# Kasli-SOC_MUX_I2C.net
KiCad netlist of a schematic drawn in Altium Designer
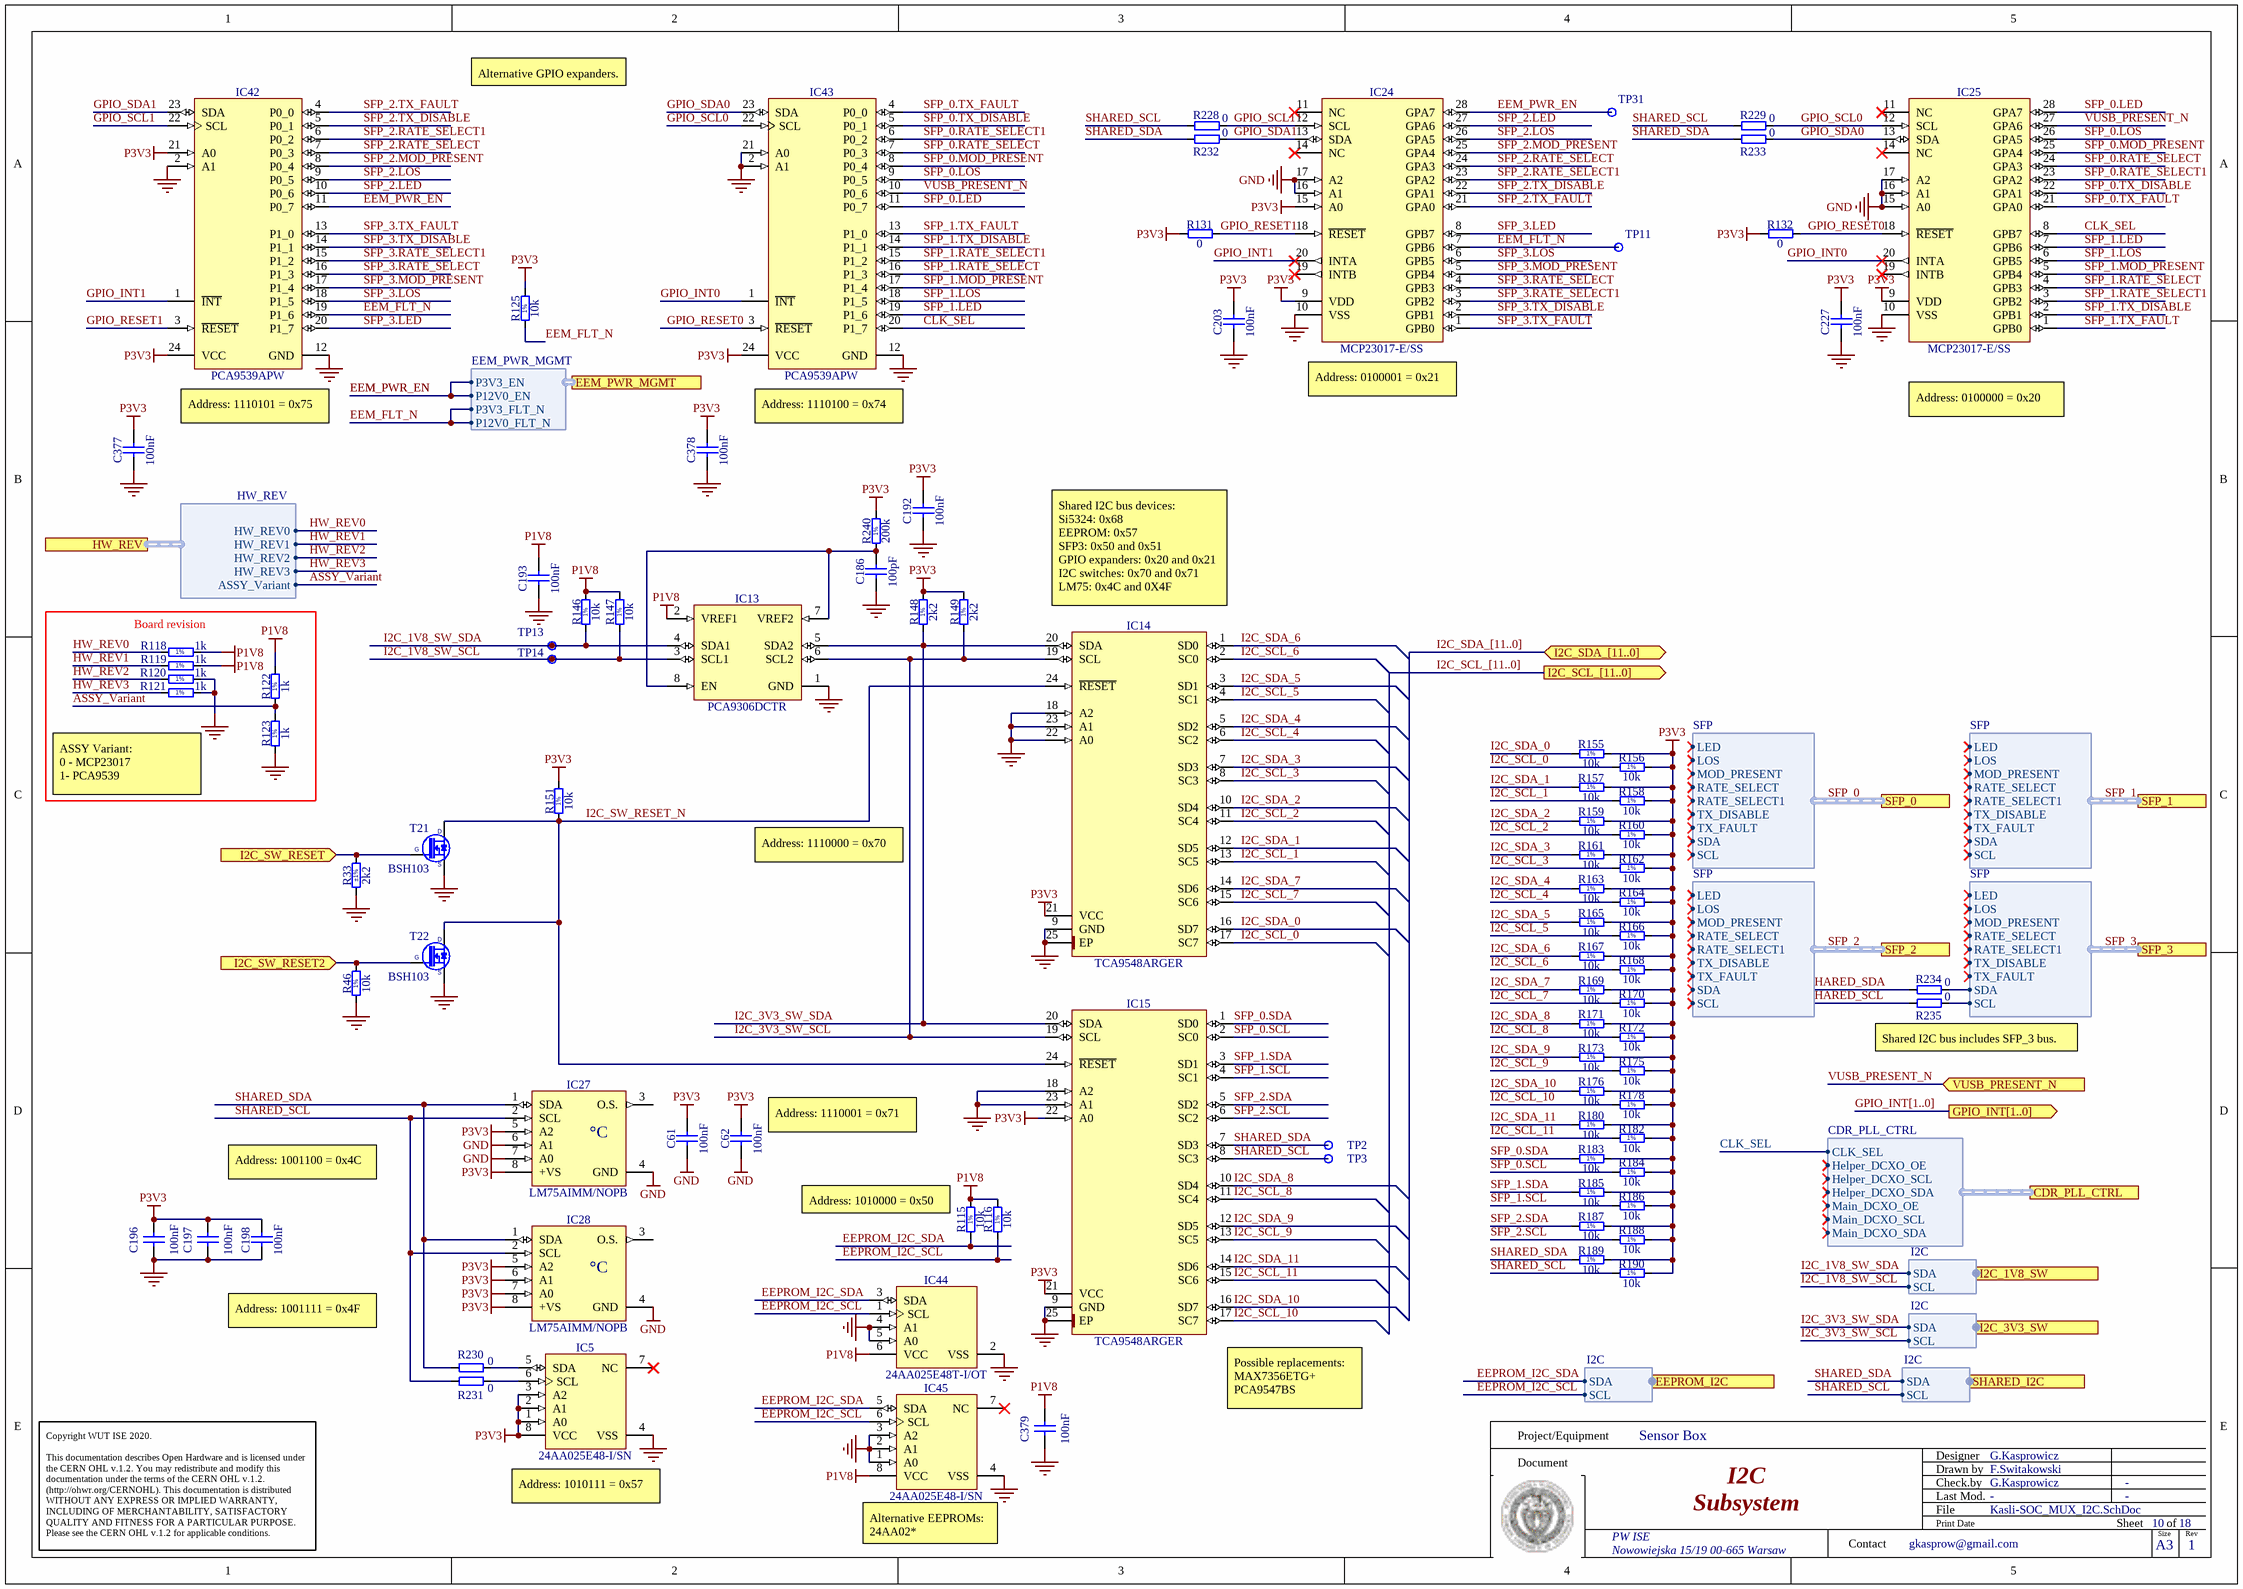
[diagram p0: Kasli-SOC_MUX_I2C.SchDoc]

(export (version "E")
  (design (tool "Eeschema 10.0.6"))
  (components
    (comp (ref "C61")
      (value "100nF")
      (footprint "CAPC1005X55N")
      (description "Non-polarised capacitor")
      (fields
        (field (name "PART NUMBER") "CC0402_100NF_16V_10%_X7R")
        (field (name "VOLTAGE") "16V")
        (field (name "AUTHOR") "CERN DEM JLC")
      )
      (libsource (lib "Capacitors") (part "Capacitor - non polarized"))
    )
    (comp (ref "C62")
      (value "100nF")
      (footprint "CAPC1005X55N")
      (description "Non-polarised capacitor")
      (fields
        (field (name "PART NUMBER") "CC0402_100NF_16V_10%_X7R")
        (field (name "VOLTAGE") "16V")
        (field (name "AUTHOR") "CERN DEM JLC")
      )
      (libsource (lib "Capacitors") (part "Capacitor - non polarized"))
    )
    (comp (ref "C186")
      (value "100pF")
      (footprint "CAPC1005X55N")
      (description "Non-polarised capacitor")
      (fields
        (field (name "PART NUMBER") "CC0402_100PF_50V_5%_C0G")
        (field (name "VOLTAGE") "50V")
        (field (name "AUTHOR") "CERN DEM JLC")
      )
      (libsource (lib "Capacitors") (part "Capacitor - non polarized"))
    )
    (comp (ref "C192")
      (value "100nF")
      (footprint "CAPC1005X55N")
      (description "Non-polarised capacitor")
      (fields
        (field (name "PART NUMBER") "CC0402_100NF_16V_10%_X7R")
        (field (name "VOLTAGE") "16V")
        (field (name "AUTHOR") "CERN DEM JLC")
      )
      (libsource (lib "Capacitors") (part "Capacitor - non polarized"))
    )
    (comp (ref "C193")
      (value "100nF")
      (footprint "CAPC1005X55N")
      (description "Non-polarised capacitor")
      (fields
        (field (name "PART NUMBER") "CC0402_100NF_16V_10%_X7R")
        (field (name "VOLTAGE") "16V")
        (field (name "AUTHOR") "CERN DEM JLC")
      )
      (libsource (lib "Capacitors") (part "Capacitor - non polarized"))
    )
    (comp (ref "C196")
      (value "100nF")
      (footprint "CAPC0603X33N")
      (description "Non-polarised capacitor")
      (fields
        (field (name "PART NUMBER") "CC0201_100NF_6.3V_10%_X5R")
        (field (name "VOLTAGE") "6.3V")
        (field (name "AUTHOR") "CERN DEM JLC")
      )
      (libsource (lib "Capacitors") (part "Capacitor - non polarized"))
    )
    (comp (ref "C197")
      (value "100nF")
      (footprint "CAPC0603X33N")
      (description "Non-polarised capacitor")
      (fields
        (field (name "PART NUMBER") "CC0201_100NF_6.3V_10%_X5R")
        (field (name "VOLTAGE") "6.3V")
        (field (name "AUTHOR") "CERN DEM JLC")
      )
      (libsource (lib "Capacitors") (part "Capacitor - non polarized"))
    )
    (comp (ref "C198")
      (value "100nF")
      (footprint "CAPC1005X55N")
      (description "Non-polarised capacitor")
      (fields
        (field (name "PART NUMBER") "CC0402_100NF_16V_10%_X7R")
        (field (name "VOLTAGE") "16V")
        (field (name "AUTHOR") "CERN DEM JLC")
      )
      (libsource (lib "Capacitors") (part "Capacitor - non polarized"))
    )
    (comp (ref "C203")
      (value "100nF")
      (footprint "CAPC1005X55N")
      (description "Non-polarised capacitor")
      (fields
        (field (name "PART NUMBER") "CC0402_100NF_16V_10%_X7R")
        (field (name "VOLTAGE") "16V")
        (field (name "AUTHOR") "CERN DEM JLC")
      )
      (libsource (lib "Capacitors") (part "Capacitor - non polarized"))
    )
    (comp (ref "C227")
      (value "100nF")
      (footprint "CAPC1005X55N")
      (description "Non-polarised capacitor")
      (fields
        (field (name "PART NUMBER") "CC0402_100NF_16V_10%_X7R")
        (field (name "VOLTAGE") "16V")
        (field (name "AUTHOR") "CERN DEM JLC")
      )
      (libsource (lib "Capacitors") (part "Capacitor - non polarized"))
    )
    (comp (ref "C377")
      (value "100nF")
      (footprint "CAPC1005X55N")
      (description "Non-polarised capacitor")
      (fields
        (field (name "PART NUMBER") "CC0402_100NF_16V_10%_X7R")
        (field (name "VOLTAGE") "16V")
        (field (name "AUTHOR") "CERN DEM JLC")
      )
      (libsource (lib "Capacitors") (part "Capacitor - non polarized"))
    )
    (comp (ref "C378")
      (value "100nF")
      (footprint "CAPC1005X55N")
      (description "Non-polarised capacitor")
      (fields
        (field (name "PART NUMBER") "CC0402_100NF_16V_10%_X7R")
        (field (name "VOLTAGE") "16V")
        (field (name "AUTHOR") "CERN DEM JLC")
      )
      (libsource (lib "Capacitors") (part "Capacitor - non polarized"))
    )
    (comp (ref "C379")
      (value "100nF")
      (footprint "CAPC1005X55N")
      (description "Non-polarised capacitor")
      (fields
        (field (name "PART NUMBER") "CC0402_100NF_16V_10%_X5R")
        (field (name "VOLTAGE") "16V")
        (field (name "AUTHOR") "CERN DEM JLC")
      )
      (libsource (lib "Capacitors") (part "Capacitor - non polarized"))
    )
    (comp (ref "IC5")
      (value "24AA025E48-I/SN")
      (footprint "SOIC127P600X175-8N")
      (description "1.7V-5.5V, 2K I2C™ Serial EEPROMs with EUI-48™ Node Identity")
      (fields (field (name "MANUFACTURER") "MICROCHIP TECHNOLOGY") (field (name "AUTHOR") "CERN DEM MR"))
      (libsource (lib "ICs And Semiconductors") (part "24AA025E48-I/SN"))
    )
    (comp (ref "IC13")
      (value "PCA9306DCTR")
      (footprint "SOP65P400X130-8N")
      (description "Dual Bidirectional I2C Bus And SMBus Voltage-Level Translator")
      (fields (field (name "MANUFACTURER") "TEXAS INSTRUMENTS") (field (name "AUTHOR") "CERN DEM JLC"))
      (libsource (lib "ICs And Semiconductors") (part "PCA9306D"))
    )
    (comp (ref "IC14")
      (value "TCA9548ARGER")
      (footprint "QFN50P400X400X100-25N-S220")
      (description "Low Voltage 8-Channel I2C Switch With Reset")
      (fields (field (name "MANUFACTURER") "TEXAS INSTRUMENTS") (field (name "AUTHOR") "CERN DEM JLC"))
      (libsource (lib "ICs And Semiconductors") (part "TCA9548ARGER"))
    )
    (comp (ref "IC15")
      (value "TCA9548ARGER")
      (footprint "QFN50P400X400X100-25N-S220")
      (description "Low Voltage 8-Channel I2C Switch With Reset")
      (fields (field (name "MANUFACTURER") "TEXAS INSTRUMENTS") (field (name "AUTHOR") "CERN DEM JLC"))
      (libsource (lib "ICs And Semiconductors") (part "TCA9548ARGER"))
    )
    (comp (ref "IC24")
      (value "MCP23017-E/SS")
      (footprint "SOP65P780X200-28N")
      (description "16-bit I/O Port Expander With Serial Interface")
      (fields (field (name "MANUFACTURER") "MICROCHIP TECHNOLOGY") (field (name "AUTHOR") "CERN DEM JLC"))
      (libsource (lib "ICs And Semiconductors") (part "MCP23017-E/SS"))
    )
    (comp (ref "IC25")
      (value "MCP23017-E/SS")
      (footprint "SOP65P780X200-28N")
      (description "16-bit I/O Port Expander With Serial Interface")
      (fields (field (name "MANUFACTURER") "MICROCHIP TECHNOLOGY") (field (name "AUTHOR") "CERN DEM JLC"))
      (libsource (lib "ICs And Semiconductors") (part "MCP23017-E/SS"))
    )
    (comp (ref "IC27")
      (value "LM75AIMM/NOPB")
      (footprint "SOP65P490X109-8N")
      (description "Digital Temperature Sensor and Thermal Watchdog with Two-Wire Interface")
      (fields (field (name "MANUFACTURER") "TEXAS INSTRUMENTS") (field (name "AUTHOR") "CERN DEM JLC"))
      (libsource (lib "ICs And Semiconductors") (part "LM75"))
    )
    (comp (ref "IC28")
      (value "LM75AIMM/NOPB")
      (footprint "SOP65P490X109-8N")
      (description "Digital Temperature Sensor and Thermal Watchdog with Two-Wire Interface")
      (fields (field (name "MANUFACTURER") "TEXAS INSTRUMENTS") (field (name "AUTHOR") "CERN DEM JLC"))
      (libsource (lib "ICs And Semiconductors") (part "LM75"))
    )
    (comp (ref "IC42")
      (value "PCA9539APW")
      (footprint "SOP65P640X110-24N")
      (description "Low-Voltage 16-Bit I2C-Bus I/O Port with Interrupt and Reset")
      (fields (field (name "MANUFACTURER") "NXP SEMICONDUCTORS") (field (name "AUTHOR") "CERN DEM JMW"))
      (libsource (lib "ICs And Semiconductors") (part "PCA9539APW"))
    )
    (comp (ref "IC43")
      (value "PCA9539APW")
      (footprint "SOP65P640X110-24N")
      (description "Low-Voltage 16-Bit I2C-Bus I/O Port with Interrupt and Reset")
      (fields (field (name "MANUFACTURER") "NXP SEMICONDUCTORS") (field (name "AUTHOR") "CERN DEM JMW"))
      (libsource (lib "ICs And Semiconductors") (part "PCA9539APW"))
    )
    (comp (ref "IC44")
      (value "24AA025E48T-I/OT")
      (footprint "SOT95P280X145-6N")
      (description "1.7V-5.5V, 2K I2C Serial EEPROM With EUI-48 Node Identity")
      (fields (field (name "MANUFACTURER") "MICROCHIP TECHNOLOGY") (field (name "AUTHOR") "CERN DEM BC"))
      (libsource (lib "ICs And Semiconductors") (part "24AA025E48T-I/OT"))
    )
    (comp (ref "IC45")
      (value "24AA025E48-I/SN")
      (footprint "SOIC127P600X175-8N")
      (description "1.7V-5.5V, 2K I2C™ Serial EEPROMs with EUI-48™ Node Identity")
      (fields (field (name "MANUFACTURER") "MICROCHIP TECHNOLOGY") (field (name "AUTHOR") "CERN DEM MR"))
      (libsource (lib "ICs And Semiconductors") (part "24AA025E48-I/SN"))
    )
    (comp (ref "R33")
      (value "2k2")
      (footprint "RESC1005X40N")
      (description "Resistor - 1%")
      (fields
        (field (name "TOLERANCE") "±1%")
        (field (name "PART NUMBER") "R0402_2K2_1%_0.0625W_100PPM")
        (field (name "POWER") "0.0625W")
        (field (name "AUTHOR") "CERN DEM JLC")
      )
      (libsource (lib "Resistors") (part "Resistor - 1%"))
    )
    (comp (ref "R46")
      (value "10k")
      (footprint "RESC1005X40N")
      (description "Resistor - 1%")
      (fields
        (field (name "PART NUMBER") "R0402_10K_1%_0.0625W_100PPM")
        (field (name "POWER") "0.0625W")
        (field (name "AUTHOR") "CERN DEM JLC")
      )
      (libsource (lib "Resistors") (part "Resistor - 1%"))
    )
    (comp (ref "R115")
      (value "10k")
      (footprint "RESC1005X40N")
      (description "Resistor - 1%")
      (fields
        (field (name "PART NUMBER") "R0402_10K_1%_0.0625W_100PPM")
        (field (name "POWER") "0.0625W")
        (field (name "AUTHOR") "CERN DEM JLC")
      )
      (libsource (lib "Resistors") (part "Resistor - 1%"))
    )
    (comp (ref "R116")
      (value "10k")
      (footprint "RESC1005X40N")
      (description "Resistor - 1%")
      (fields
        (field (name "PART NUMBER") "R0402_10K_1%_0.0625W_100PPM")
        (field (name "POWER") "0.0625W")
        (field (name "AUTHOR") "CERN DEM JLC")
      )
      (libsource (lib "Resistors") (part "Resistor - 1%"))
    )
    (comp (ref "R118")
      (value "1k")
      (footprint "RESC1005X40N")
      (description "Resistor - 1%")
      (fields
        (field (name "PART NUMBER") "R0402_1K_1%_0.0625W_100PPM")
        (field (name "POWER") "0.0625W")
        (field (name "AUTHOR") "CERN DEM JLC")
      )
      (libsource (lib "Resistors") (part "Resistor - 1%"))
    )
    (comp (ref "R119")
      (value "1k")
      (footprint "RESC1005X40N")
      (description "Resistor - 1%")
      (fields
        (field (name "PART NUMBER") "R0402_1K_1%_0.0625W_100PPM")
        (field (name "POWER") "0.0625W")
        (field (name "AUTHOR") "CERN DEM JLC")
      )
      (libsource (lib "Resistors") (part "Resistor - 1%"))
    )
    (comp (ref "R120")
      (value "1k")
      (footprint "RESC1005X40N")
      (description "Resistor - 1%")
      (fields
        (field (name "PART NUMBER") "R0402_1K_1%_0.0625W_100PPM")
        (field (name "POWER") "0.0625W")
        (field (name "AUTHOR") "CERN DEM JLC")
      )
      (libsource (lib "Resistors") (part "Resistor - 1%"))
    )
    (comp (ref "R121")
      (value "1k")
      (footprint "RESC1005X40N")
      (description "Resistor - 1%")
      (fields
        (field (name "PART NUMBER") "R0402_1K_1%_0.0625W_100PPM")
        (field (name "POWER") "0.0625W")
        (field (name "AUTHOR") "CERN DEM JLC")
      )
      (libsource (lib "Resistors") (part "Resistor - 1%"))
    )
    (comp (ref "R122")
      (value "1k")
      (footprint "RESC1005X40N")
      (description "Resistor - 1%")
      (fields
        (field (name "PART NUMBER") "R0402_1K_1%_0.0625W_100PPM")
        (field (name "POWER") "0.0625W")
        (field (name "AUTHOR") "CERN DEM JLC")
      )
      (libsource (lib "Resistors") (part "Resistor - 1%"))
    )
    (comp (ref "R123")
      (value "1k")
      (footprint "RESC1005X40N")
      (description "Resistor - 1%")
      (fields
        (field (name "PART NUMBER") "R0402_1K_1%_0.0625W_100PPM")
        (field (name "POWER") "0.0625W")
        (field (name "AUTHOR") "CERN DEM JLC")
      )
      (libsource (lib "Resistors") (part "Resistor - 1%"))
    )
    (comp (ref "R125")
      (value "10k")
      (footprint "RESC1005X40N")
      (description "Resistor - 1%")
      (fields
        (field (name "PART NUMBER") "R0402_10K_1%_0.0625W_100PPM")
        (field (name "POWER") "0.0625W")
        (field (name "AUTHOR") "CERN DEM JLC")
      )
      (libsource (lib "Resistors") (part "Resistor - 1%"))
    )
    (comp (ref "R131")
      (value "0")
      (footprint "RESC1005X40N")
      (description "Resistor")
      (fields
        (field (name "PART NUMBER") "R0402_0R_JUMPER")
        (field (name "MANUFACTURER") "GENERIC")
        (field (name "AUTHOR") "CERN DEM JLC")
      )
      (libsource (lib "Resistors") (part "Resistor"))
    )
    (comp (ref "R132")
      (value "0")
      (footprint "RESC1005X40N")
      (description "Resistor")
      (fields
        (field (name "PART NUMBER") "R0402_0R_JUMPER")
        (field (name "MANUFACTURER") "GENERIC")
        (field (name "AUTHOR") "CERN DEM JLC")
      )
      (libsource (lib "Resistors") (part "Resistor"))
    )
    (comp (ref "R146")
      (value "10k")
      (footprint "RESC1005X40N")
      (description "Resistor - 1%")
      (fields
        (field (name "PART NUMBER") "R0402_10K_1%_0.0625W_100PPM")
        (field (name "POWER") "0.0625W")
        (field (name "AUTHOR") "CERN DEM JLC")
      )
      (libsource (lib "Resistors") (part "Resistor - 1%"))
    )
    (comp (ref "R147")
      (value "10k")
      (footprint "RESC1005X40N")
      (description "Resistor - 1%")
      (fields
        (field (name "PART NUMBER") "R0402_10K_1%_0.0625W_100PPM")
        (field (name "POWER") "0.0625W")
        (field (name "AUTHOR") "CERN DEM JLC")
      )
      (libsource (lib "Resistors") (part "Resistor - 1%"))
    )
    (comp (ref "R148")
      (value "2k2")
      (footprint "RESC1005X40N")
      (description "Resistor - 1%")
      (fields
        (field (name "PART NUMBER") "R0402_2K2_1%_0.0625W_100PPM")
        (field (name "POWER") "0.0625W")
        (field (name "AUTHOR") "CERN DEM JLC")
      )
      (libsource (lib "Resistors") (part "Resistor - 1%"))
    )
    (comp (ref "R149")
      (value "2k2")
      (footprint "RESC1005X40N")
      (description "Resistor - 1%")
      (fields
        (field (name "PART NUMBER") "R0402_2K2_1%_0.0625W_100PPM")
        (field (name "POWER") "0.0625W")
        (field (name "AUTHOR") "CERN DEM JLC")
      )
      (libsource (lib "Resistors") (part "Resistor - 1%"))
    )
    (comp (ref "R151")
      (value "10k")
      (footprint "RESC1005X40N")
      (description "Resistor - 1%")
      (fields
        (field (name "PART NUMBER") "R0402_10K_1%_0.0625W_100PPM")
        (field (name "POWER") "0.0625W")
        (field (name "AUTHOR") "CERN DEM JLC")
      )
      (libsource (lib "Resistors") (part "Resistor - 1%"))
    )
    (comp (ref "R155")
      (value "10k")
      (footprint "RESC1005X40N")
      (description "Resistor - 1%")
      (fields
        (field (name "PART NUMBER") "R0402_10K_1%_0.0625W_100PPM")
        (field (name "POWER") "0.0625W")
        (field (name "AUTHOR") "CERN DEM JLC")
      )
      (libsource (lib "Resistors") (part "Resistor - 1%"))
    )
    (comp (ref "R156")
      (value "10k")
      (footprint "RESC1005X40N")
      (description "Resistor - 1%")
      (fields
        (field (name "PART NUMBER") "R0402_10K_1%_0.0625W_100PPM")
        (field (name "POWER") "0.0625W")
        (field (name "AUTHOR") "CERN DEM JLC")
      )
      (libsource (lib "Resistors") (part "Resistor - 1%"))
    )
    (comp (ref "R157")
      (value "10k")
      (footprint "RESC1005X40N")
      (description "Resistor - 1%")
      (fields
        (field (name "PART NUMBER") "R0402_10K_1%_0.0625W_100PPM")
        (field (name "POWER") "0.0625W")
        (field (name "AUTHOR") "CERN DEM JLC")
      )
      (libsource (lib "Resistors") (part "Resistor - 1%"))
    )
    (comp (ref "R158")
      (value "10k")
      (footprint "RESC1005X40N")
      (description "Resistor - 1%")
      (fields
        (field (name "PART NUMBER") "R0402_10K_1%_0.0625W_100PPM")
        (field (name "POWER") "0.0625W")
        (field (name "AUTHOR") "CERN DEM JLC")
      )
      (libsource (lib "Resistors") (part "Resistor - 1%"))
    )
    (comp (ref "R159")
      (value "10k")
      (footprint "RESC1005X40N")
      (description "Resistor - 1%")
      (fields
        (field (name "PART NUMBER") "R0402_10K_1%_0.0625W_100PPM")
        (field (name "POWER") "0.0625W")
        (field (name "AUTHOR") "CERN DEM JLC")
      )
      (libsource (lib "Resistors") (part "Resistor - 1%"))
    )
    (comp (ref "R160")
      (value "10k")
      (footprint "RESC1005X40N")
      (description "Resistor - 1%")
      (fields
        (field (name "PART NUMBER") "R0402_10K_1%_0.0625W_100PPM")
        (field (name "POWER") "0.0625W")
        (field (name "AUTHOR") "CERN DEM JLC")
      )
      (libsource (lib "Resistors") (part "Resistor - 1%"))
    )
    (comp (ref "R161")
      (value "10k")
      (footprint "RESC1005X40N")
      (description "Resistor - 1%")
      (fields
        (field (name "PART NUMBER") "R0402_10K_1%_0.0625W_100PPM")
        (field (name "POWER") "0.0625W")
        (field (name "AUTHOR") "CERN DEM JLC")
      )
      (libsource (lib "Resistors") (part "Resistor - 1%"))
    )
    (comp (ref "R162")
      (value "10k")
      (footprint "RESC1005X40N")
      (description "Resistor - 1%")
      (fields
        (field (name "PART NUMBER") "R0402_10K_1%_0.0625W_100PPM")
        (field (name "POWER") "0.0625W")
        (field (name "AUTHOR") "CERN DEM JLC")
      )
      (libsource (lib "Resistors") (part "Resistor - 1%"))
    )
    (comp (ref "R163")
      (value "10k")
      (footprint "RESC1005X40N")
      (description "Resistor - 1%")
      (fields
        (field (name "PART NUMBER") "R0402_10K_1%_0.0625W_100PPM")
        (field (name "POWER") "0.0625W")
        (field (name "AUTHOR") "CERN DEM JLC")
      )
      (libsource (lib "Resistors") (part "Resistor - 1%"))
    )
    (comp (ref "R164")
      (value "10k")
      (footprint "RESC1005X40N")
      (description "Resistor - 1%")
      (fields
        (field (name "PART NUMBER") "R0402_10K_1%_0.0625W_100PPM")
        (field (name "POWER") "0.0625W")
        (field (name "AUTHOR") "CERN DEM JLC")
      )
      (libsource (lib "Resistors") (part "Resistor - 1%"))
    )
    (comp (ref "R165")
      (value "10k")
      (footprint "RESC1005X40N")
      (description "Resistor - 1%")
      (fields
        (field (name "PART NUMBER") "R0402_10K_1%_0.0625W_100PPM")
        (field (name "POWER") "0.0625W")
        (field (name "AUTHOR") "CERN DEM JLC")
      )
      (libsource (lib "Resistors") (part "Resistor - 1%"))
    )
    (comp (ref "R166")
      (value "10k")
      (footprint "RESC1005X40N")
      (description "Resistor - 1%")
      (fields
        (field (name "PART NUMBER") "R0402_10K_1%_0.0625W_100PPM")
        (field (name "POWER") "0.0625W")
        (field (name "AUTHOR") "CERN DEM JLC")
      )
      (libsource (lib "Resistors") (part "Resistor - 1%"))
    )
    (comp (ref "R167")
      (value "10k")
      (footprint "RESC1005X40N")
      (description "Resistor - 1%")
      (fields
        (field (name "PART NUMBER") "R0402_10K_1%_0.0625W_100PPM")
        (field (name "POWER") "0.0625W")
        (field (name "AUTHOR") "CERN DEM JLC")
      )
      (libsource (lib "Resistors") (part "Resistor - 1%"))
    )
    (comp (ref "R168")
      (value "10k")
      (footprint "RESC1005X40N")
      (description "Resistor - 1%")
      (fields
        (field (name "PART NUMBER") "R0402_10K_1%_0.0625W_100PPM")
        (field (name "POWER") "0.0625W")
        (field (name "AUTHOR") "CERN DEM JLC")
      )
      (libsource (lib "Resistors") (part "Resistor - 1%"))
    )
    (comp (ref "R169")
      (value "10k")
      (footprint "RESC1005X40N")
      (description "Resistor - 1%")
      (fields
        (field (name "PART NUMBER") "R0402_10K_1%_0.0625W_100PPM")
        (field (name "POWER") "0.0625W")
        (field (name "AUTHOR") "CERN DEM JLC")
      )
      (libsource (lib "Resistors") (part "Resistor - 1%"))
    )
    (comp (ref "R170")
      (value "10k")
      (footprint "RESC1005X40N")
      (description "Resistor - 1%")
      (fields
        (field (name "PART NUMBER") "R0402_10K_1%_0.0625W_100PPM")
        (field (name "POWER") "0.0625W")
        (field (name "AUTHOR") "CERN DEM JLC")
      )
      (libsource (lib "Resistors") (part "Resistor - 1%"))
    )
    (comp (ref "R171")
      (value "10k")
      (footprint "RESC1005X40N")
      (description "Resistor - 1%")
      (fields
        (field (name "PART NUMBER") "R0402_10K_1%_0.0625W_100PPM")
        (field (name "POWER") "0.0625W")
        (field (name "AUTHOR") "CERN DEM JLC")
      )
      (libsource (lib "Resistors") (part "Resistor - 1%"))
    )
    (comp (ref "R172")
      (value "10k")
      (footprint "RESC1005X40N")
      (description "Resistor - 1%")
      (fields
        (field (name "PART NUMBER") "R0402_10K_1%_0.0625W_100PPM")
        (field (name "POWER") "0.0625W")
        (field (name "AUTHOR") "CERN DEM JLC")
      )
      (libsource (lib "Resistors") (part "Resistor - 1%"))
    )
    (comp (ref "R173")
      (value "10k")
      (footprint "RESC1005X40N")
      (description "Resistor - 1%")
      (fields
        (field (name "PART NUMBER") "R0402_10K_1%_0.0625W_100PPM")
        (field (name "POWER") "0.0625W")
        (field (name "AUTHOR") "CERN DEM JLC")
      )
      (libsource (lib "Resistors") (part "Resistor - 1%"))
    )
    (comp (ref "R175")
      (value "10k")
      (footprint "RESC1005X40N")
      (description "Resistor - 1%")
      (fields
        (field (name "PART NUMBER") "R0402_10K_1%_0.0625W_100PPM")
        (field (name "POWER") "0.0625W")
        (field (name "AUTHOR") "CERN DEM JLC")
      )
      (libsource (lib "Resistors") (part "Resistor - 1%"))
    )
    (comp (ref "R176")
      (value "10k")
      (footprint "RESC1005X40N")
      (description "Resistor - 1%")
      (fields
        (field (name "PART NUMBER") "R0402_10K_1%_0.0625W_100PPM")
        (field (name "POWER") "0.0625W")
        (field (name "AUTHOR") "CERN DEM JLC")
      )
      (libsource (lib "Resistors") (part "Resistor - 1%"))
    )
    (comp (ref "R178")
      (value "10k")
      (footprint "RESC1005X40N")
      (description "Resistor - 1%")
      (fields
        (field (name "PART NUMBER") "R0402_10K_1%_0.0625W_100PPM")
        (field (name "POWER") "0.0625W")
        (field (name "AUTHOR") "CERN DEM JLC")
      )
      (libsource (lib "Resistors") (part "Resistor - 1%"))
    )
    (comp (ref "R180")
      (value "10k")
      (footprint "RESC1005X40N")
      (description "Resistor - 1%")
      (fields
        (field (name "PART NUMBER") "R0402_10K_1%_0.0625W_100PPM")
        (field (name "POWER") "0.0625W")
        (field (name "AUTHOR") "CERN DEM JLC")
      )
      (libsource (lib "Resistors") (part "Resistor - 1%"))
    )
    (comp (ref "R182")
      (value "10k")
      (footprint "RESC1005X40N")
      (description "Resistor - 1%")
      (fields
        (field (name "PART NUMBER") "R0402_10K_1%_0.0625W_100PPM")
        (field (name "POWER") "0.0625W")
        (field (name "AUTHOR") "CERN DEM JLC")
      )
      (libsource (lib "Resistors") (part "Resistor - 1%"))
    )
    (comp (ref "R183")
      (value "10k")
      (footprint "RESC1005X40N")
      (description "Resistor - 1%")
      (fields
        (field (name "PART NUMBER") "R0402_10K_1%_0.0625W_100PPM")
        (field (name "POWER") "0.0625W")
        (field (name "AUTHOR") "CERN DEM JLC")
      )
      (libsource (lib "Resistors") (part "Resistor - 1%"))
    )
    (comp (ref "R184")
      (value "10k")
      (footprint "RESC1005X40N")
      (description "Resistor - 1%")
      (fields
        (field (name "PART NUMBER") "R0402_10K_1%_0.0625W_100PPM")
        (field (name "POWER") "0.0625W")
        (field (name "AUTHOR") "CERN DEM JLC")
      )
      (libsource (lib "Resistors") (part "Resistor - 1%"))
    )
    (comp (ref "R185")
      (value "10k")
      (footprint "RESC1005X40N")
      (description "Resistor - 1%")
      (fields
        (field (name "PART NUMBER") "R0402_10K_1%_0.0625W_100PPM")
        (field (name "POWER") "0.0625W")
        (field (name "AUTHOR") "CERN DEM JLC")
      )
      (libsource (lib "Resistors") (part "Resistor - 1%"))
    )
    (comp (ref "R186")
      (value "10k")
      (footprint "RESC1005X40N")
      (description "Resistor - 1%")
      (fields
        (field (name "PART NUMBER") "R0402_10K_1%_0.0625W_100PPM")
        (field (name "POWER") "0.0625W")
        (field (name "AUTHOR") "CERN DEM JLC")
      )
      (libsource (lib "Resistors") (part "Resistor - 1%"))
    )
    (comp (ref "R187")
      (value "10k")
      (footprint "RESC1005X40N")
      (description "Resistor - 1%")
      (fields
        (field (name "PART NUMBER") "R0402_10K_1%_0.0625W_100PPM")
        (field (name "POWER") "0.0625W")
        (field (name "AUTHOR") "CERN DEM JLC")
      )
      (libsource (lib "Resistors") (part "Resistor - 1%"))
    )
    (comp (ref "R188")
      (value "10k")
      (footprint "RESC1005X40N")
      (description "Resistor - 1%")
      (fields
        (field (name "PART NUMBER") "R0402_10K_1%_0.0625W_100PPM")
        (field (name "POWER") "0.0625W")
        (field (name "AUTHOR") "CERN DEM JLC")
      )
      (libsource (lib "Resistors") (part "Resistor - 1%"))
    )
    (comp (ref "R189")
      (value "10k")
      (footprint "RESC1005X40N")
      (description "Resistor - 1%")
      (fields
        (field (name "PART NUMBER") "R0402_10K_1%_0.0625W_100PPM")
        (field (name "POWER") "0.0625W")
        (field (name "AUTHOR") "CERN DEM JLC")
      )
      (libsource (lib "Resistors") (part "Resistor - 1%"))
    )
    (comp (ref "R190")
      (value "10k")
      (footprint "RESC1005X40N")
      (description "Resistor - 1%")
      (fields
        (field (name "PART NUMBER") "R0402_10K_1%_0.0625W_100PPM")
        (field (name "POWER") "0.0625W")
        (field (name "AUTHOR") "CERN DEM JLC")
      )
      (libsource (lib "Resistors") (part "Resistor - 1%"))
    )
    (comp (ref "R228")
      (value "0")
      (footprint "RESC1005X40N")
      (description "Resistor")
      (fields
        (field (name "PART NUMBER") "R0402_0R_JUMPER")
        (field (name "MANUFACTURER") "GENERIC")
        (field (name "AUTHOR") "CERN DEM JLC")
      )
      (libsource (lib "Resistors") (part "Resistor"))
    )
    (comp (ref "R229")
      (value "0")
      (footprint "RESC1005X40N")
      (description "Resistor")
      (fields
        (field (name "PART NUMBER") "R0402_0R_JUMPER")
        (field (name "MANUFACTURER") "GENERIC")
        (field (name "AUTHOR") "CERN DEM JLC")
      )
      (libsource (lib "Resistors") (part "Resistor"))
    )
    (comp (ref "R230")
      (value "0")
      (footprint "RESC1005X40N")
      (description "Resistor")
      (fields
        (field (name "PART NUMBER") "R0402_0R_JUMPER")
        (field (name "MANUFACTURER") "GENERIC")
        (field (name "AUTHOR") "CERN DEM JLC")
      )
      (libsource (lib "Resistors") (part "Resistor"))
    )
    (comp (ref "R231")
      (value "0")
      (footprint "RESC1005X40N")
      (description "Resistor")
      (fields
        (field (name "PART NUMBER") "R0402_0R_JUMPER")
        (field (name "MANUFACTURER") "GENERIC")
        (field (name "AUTHOR") "CERN DEM JLC")
      )
      (libsource (lib "Resistors") (part "Resistor"))
    )
    (comp (ref "R232")
      (value "0")
      (footprint "RESC1005X40N")
      (description "Resistor")
      (fields
        (field (name "PART NUMBER") "R0402_0R_JUMPER")
        (field (name "MANUFACTURER") "GENERIC")
        (field (name "AUTHOR") "CERN DEM JLC")
      )
      (libsource (lib "Resistors") (part "Resistor"))
    )
    (comp (ref "R233")
      (value "0")
      (footprint "RESC1005X40N")
      (description "Resistor")
      (fields
        (field (name "PART NUMBER") "R0402_0R_JUMPER")
        (field (name "MANUFACTURER") "GENERIC")
        (field (name "AUTHOR") "CERN DEM JLC")
      )
      (libsource (lib "Resistors") (part "Resistor"))
    )
    (comp (ref "R234")
      (value "0")
      (footprint "RESC1005X40N")
      (description "Resistor")
      (fields
        (field (name "PART NUMBER") "R0402_0R_JUMPER")
        (field (name "MANUFACTURER") "GENERIC")
        (field (name "AUTHOR") "CERN DEM JLC")
      )
      (libsource (lib "Resistors") (part "Resistor"))
    )
    (comp (ref "R235")
      (value "0")
      (footprint "RESC1005X40N")
      (description "Resistor")
      (fields
        (field (name "PART NUMBER") "R0402_0R_JUMPER")
        (field (name "MANUFACTURER") "GENERIC")
        (field (name "AUTHOR") "CERN DEM JLC")
      )
      (libsource (lib "Resistors") (part "Resistor"))
    )
    (comp (ref "R240")
      (value "200k")
      (footprint "RESC1005X40N")
      (description "Resistor - 1%")
      (fields
        (field (name "PART NUMBER") "R0402_200K_1%_0.0625W_100PPM")
        (field (name "POWER") "0.0625W")
        (field (name "AUTHOR") "CERN DEM JLC")
      )
      (libsource (lib "Resistors") (part "Resistor - 1%"))
    )
    (comp (ref "T21")
      (value "BSH103")
      (footprint "SOT95P230X110-3N")
      (description "N-CHANNEL MOSFET WITH DIODE")
      (fields (field (name "MANUFACTURER") "NEXPERIA") (field (name "AUTHOR") "CERN DEM JLC"))
      (libsource (lib "ICs And Semiconductors") (part "N-MOSFET-D 1G 2S 3D"))
    )
    (comp (ref "T22")
      (value "BSH103")
      (footprint "SOT95P230X110-3N")
      (description "N-CHANNEL MOSFET WITH DIODE")
      (fields (field (name "MANUFACTURER") "NEXPERIA") (field (name "AUTHOR") "CERN DEM JLC"))
      (libsource (lib "ICs And Semiconductors") (part "N-MOSFET-D 1G 2S 3D"))
    )
    (comp (ref "TP2")
      (value "Si5324 I2C SDA")
      (footprint "TPS127")
      (description "Test Point")
      (fields (field (name "PART NUMBER") "SMD_PAD_1.27X1.27MM") (field (name "AUTHOR") "CERN DEM JLC"))
      (libsource (lib "Eletro-mechanical") (part "Test Point"))
    )
    (comp (ref "TP3")
      (value "Si5324 I2C SCL")
      (footprint "TPS127")
      (description "Test Point")
      (fields (field (name "PART NUMBER") "SMD_PAD_1.27X1.27MM") (field (name "AUTHOR") "CERN DEM JLC"))
      (libsource (lib "Eletro-mechanical") (part "Test Point"))
    )
    (comp (ref "TP11")
      (value "I2C SW SCL")
      (footprint "TPS127")
      (description "Test Point")
      (fields (field (name "PART NUMBER") "SMD_PAD_1.27X1.27MM") (field (name "AUTHOR") "CERN DEM JLC"))
      (libsource (lib "Eletro-mechanical") (part "Test Point"))
    )
    (comp (ref "TP13")
      (value "I2C SW SDA")
      (footprint "TPS127")
      (description "Test Point")
      (fields (field (name "PART NUMBER") "SMD_PAD_1.27X1.27MM") (field (name "AUTHOR") "CERN DEM JLC"))
      (libsource (lib "Eletro-mechanical") (part "Test Point"))
    )
    (comp (ref "TP14")
      (value "I2C SW SCL")
      (footprint "TPS127")
      (description "Test Point")
      (fields (field (name "PART NUMBER") "SMD_PAD_1.27X1.27MM") (field (name "AUTHOR") "CERN DEM JLC"))
      (libsource (lib "Eletro-mechanical") (part "Test Point"))
    )
    (comp (ref "TP31")
      (value "I2C SW SCL")
      (footprint "TPS127")
      (description "Test Point")
      (fields (field (name "PART NUMBER") "SMD_PAD_1.27X1.27MM") (field (name "AUTHOR") "CERN DEM JLC"))
      (libsource (lib "Eletro-mechanical") (part "Test Point"))
    )
  )
  (nets
    (net (code "9") (name "/ASSY_Variant") (class "Default")
      (node (ref "R122") (pin "1") (pinfunction "1_1") (pintype "passive"))
      (node (ref "R123") (pin "2") (pinfunction "2_2") (pintype "passive"))
    )
    (net (code "10") (name "/CLK_SEL") (class "Default")
      (node (ref "IC25") (pin "8") (pinfunction "GPB7_8") (pintype "bidirectional"))
      (node (ref "IC43") (pin "20") (pinfunction "P1_7_20") (pintype "bidirectional"))
    )
    (net (code "11") (name "/EEM_FLT_N") (class "Default")
      (node (ref "IC24") (pin "7") (pinfunction "GPB6_7") (pintype "bidirectional"))
      (node (ref "IC42") (pin "19") (pinfunction "P1_6_19") (pintype "bidirectional"))
      (node (ref "R125") (pin "1") (pinfunction "1_1") (pintype "passive"))
      (node (ref "TP11") (pin "1") (pinfunction "1_1") (pintype "bidirectional"))
    )
    (net (code "12") (name "/EEM_PWR_EN") (class "Default")
      (node (ref "IC24") (pin "28") (pinfunction "GPA7_28") (pintype "bidirectional"))
      (node (ref "IC42") (pin "11") (pinfunction "P0_7_11") (pintype "bidirectional"))
      (node (ref "TP31") (pin "1") (pinfunction "1_1") (pintype "bidirectional"))
    )
    (net (code "13") (name "/EEPROM_I2C_SCL") (class "Default")
      (node (ref "IC44") (pin "1") (pinfunction "SCL_1") (pintype "input"))
      (node (ref "IC45") (pin "6") (pinfunction "SCL_6") (pintype "input"))
      (node (ref "R116") (pin "1") (pinfunction "1_1") (pintype "passive"))
    )
    (net (code "14") (name "/EEPROM_I2C_SDA") (class "Default")
      (node (ref "IC44") (pin "3") (pinfunction "SDA_3") (pintype "bidirectional"))
      (node (ref "IC45") (pin "5") (pinfunction "SDA_5") (pintype "bidirectional"))
      (node (ref "R115") (pin "1") (pinfunction "1_1") (pintype "passive"))
    )
    (net (code "15") (name "/GPIO_INT0") (class "Default")
      (node (ref "IC25") (pin "20") (pinfunction "INTA_20") (pintype "output"))
      (node (ref "IC43") (pin "1") (pinfunction "~{INT}_1") (pintype "open_collector"))
    )
    (net (code "16") (name "/GPIO_INT1") (class "Default")
      (node (ref "IC24") (pin "20") (pinfunction "INTA_20") (pintype "output"))
      (node (ref "IC42") (pin "1") (pinfunction "~{INT}_1") (pintype "open_collector"))
    )
    (net (code "18") (name "/GPIO_RESET0") (class "Default")
      (node (ref "IC25") (pin "18") (pinfunction "~{RESET}_18") (pintype "input"))
      (node (ref "IC43") (pin "3") (pinfunction "~{RESET}_3") (pintype "input"))
      (node (ref "R132") (pin "2") (pinfunction "2_2") (pintype "passive"))
    )
    (net (code "19") (name "/GPIO_RESET1") (class "Default")
      (node (ref "IC24") (pin "18") (pinfunction "~{RESET}_18") (pintype "input"))
      (node (ref "IC42") (pin "3") (pinfunction "~{RESET}_3") (pintype "input"))
      (node (ref "R131") (pin "2") (pinfunction "2_2") (pintype "passive"))
    )
    (net (code "20") (name "/GPIO_SCL0") (class "Default")
      (node (ref "IC25") (pin "12") (pinfunction "SCL_12") (pintype "input"))
      (node (ref "IC43") (pin "22") (pinfunction "SCL_22") (pintype "input"))
      (node (ref "R229") (pin "2") (pinfunction "2_2") (pintype "passive"))
    )
    (net (code "21") (name "/GPIO_SCL1") (class "Default")
      (node (ref "IC24") (pin "12") (pinfunction "SCL_12") (pintype "input"))
      (node (ref "IC42") (pin "22") (pinfunction "SCL_22") (pintype "input"))
      (node (ref "R228") (pin "2") (pinfunction "2_2") (pintype "passive"))
    )
    (net (code "22") (name "/GPIO_SDA0") (class "Default")
      (node (ref "IC25") (pin "13") (pinfunction "SDA_13") (pintype "bidirectional"))
      (node (ref "IC43") (pin "23") (pinfunction "SDA_23") (pintype "bidirectional"))
      (node (ref "R233") (pin "2") (pinfunction "2_2") (pintype "passive"))
    )
    (net (code "23") (name "/GPIO_SDA1") (class "Default")
      (node (ref "IC24") (pin "13") (pinfunction "SDA_13") (pintype "bidirectional"))
      (node (ref "IC42") (pin "23") (pinfunction "SDA_23") (pintype "bidirectional"))
      (node (ref "R232") (pin "2") (pinfunction "2_2") (pintype "passive"))
    )
    (net (code "24") (name "/HW_REV0") (class "Default")
      (node (ref "R118") (pin "1") (pinfunction "1_1") (pintype "passive"))
    )
    (net (code "25") (name "/HW_REV1") (class "Default")
      (node (ref "R119") (pin "1") (pinfunction "1_1") (pintype "passive"))
    )
    (net (code "26") (name "/HW_REV2") (class "Default")
      (node (ref "R120") (pin "1") (pinfunction "1_1") (pintype "passive"))
    )
    (net (code "27") (name "/HW_REV3") (class "Default")
      (node (ref "R121") (pin "1") (pinfunction "1_1") (pintype "passive"))
    )
    (net (code "28") (name "/I2C_1V8_SW_SCL") (class "Default")
      (node (ref "IC13") (pin "3") (pinfunction "SCL1_3") (pintype "bidirectional"))
      (node (ref "R147") (pin "1") (pinfunction "1_1") (pintype "passive"))
      (node (ref "TP14") (pin "1") (pinfunction "1_1") (pintype "bidirectional"))
    )
    (net (code "29") (name "/I2C_1V8_SW_SDA") (class "Default")
      (node (ref "IC13") (pin "4") (pinfunction "SDA1_4") (pintype "bidirectional"))
      (node (ref "R146") (pin "1") (pinfunction "1_1") (pintype "passive"))
      (node (ref "TP13") (pin "1") (pinfunction "1_1") (pintype "bidirectional"))
    )
    (net (code "30") (name "/I2C_3V3_SW_SCL") (class "Default")
      (node (ref "IC13") (pin "6") (pinfunction "SCL2_6") (pintype "bidirectional"))
      (node (ref "IC14") (pin "19") (pinfunction "SCL_19") (pintype "bidirectional"))
      (node (ref "IC15") (pin "19") (pinfunction "SCL_19") (pintype "bidirectional"))
      (node (ref "R149") (pin "1") (pinfunction "1_1") (pintype "passive"))
    )
    (net (code "31") (name "/I2C_3V3_SW_SDA") (class "Default")
      (node (ref "IC13") (pin "5") (pinfunction "SDA2_5") (pintype "bidirectional"))
      (node (ref "IC14") (pin "20") (pinfunction "SDA_20") (pintype "bidirectional"))
      (node (ref "IC15") (pin "20") (pinfunction "SDA_20") (pintype "bidirectional"))
      (node (ref "R148") (pin "1") (pinfunction "1_1") (pintype "passive"))
    )
    (net (code "32") (name "/I2C_SCL_0") (class "Default")
      (node (ref "IC14") (pin "17") (pinfunction "SC7_17") (pintype "bidirectional"))
      (node (ref "R156") (pin "1") (pinfunction "1_1") (pintype "passive"))
    )
    (net (code "33") (name "/I2C_SCL_1") (class "Default")
      (node (ref "IC14") (pin "13") (pinfunction "SC5_13") (pintype "bidirectional"))
      (node (ref "R158") (pin "1") (pinfunction "1_1") (pintype "passive"))
    )
    (net (code "34") (name "/I2C_SCL_2") (class "Default")
      (node (ref "IC14") (pin "11") (pinfunction "SC4_11") (pintype "bidirectional"))
      (node (ref "R160") (pin "1") (pinfunction "1_1") (pintype "passive"))
    )
    (net (code "35") (name "/I2C_SCL_3") (class "Default")
      (node (ref "IC14") (pin "8") (pinfunction "SC3_8") (pintype "bidirectional"))
      (node (ref "R162") (pin "1") (pinfunction "1_1") (pintype "passive"))
    )
    (net (code "36") (name "/I2C_SCL_4") (class "Default")
      (node (ref "IC14") (pin "6") (pinfunction "SC2_6") (pintype "bidirectional"))
      (node (ref "R164") (pin "1") (pinfunction "1_1") (pintype "passive"))
    )
    (net (code "37") (name "/I2C_SCL_5") (class "Default")
      (node (ref "IC14") (pin "4") (pinfunction "SC1_4") (pintype "bidirectional"))
      (node (ref "R166") (pin "1") (pinfunction "1_1") (pintype "passive"))
    )
    (net (code "38") (name "/I2C_SCL_6") (class "Default")
      (node (ref "IC14") (pin "2") (pinfunction "SC0_2") (pintype "bidirectional"))
      (node (ref "R168") (pin "1") (pinfunction "1_1") (pintype "passive"))
    )
    (net (code "39") (name "/I2C_SCL_7") (class "Default")
      (node (ref "IC14") (pin "15") (pinfunction "SC6_15") (pintype "bidirectional"))
      (node (ref "R170") (pin "1") (pinfunction "1_1") (pintype "passive"))
    )
    (net (code "40") (name "/I2C_SCL_8") (class "Default")
      (node (ref "IC15") (pin "11") (pinfunction "SC4_11") (pintype "bidirectional"))
      (node (ref "R172") (pin "1") (pinfunction "1_1") (pintype "passive"))
    )
    (net (code "41") (name "/I2C_SCL_9") (class "Default")
      (node (ref "IC15") (pin "13") (pinfunction "SC5_13") (pintype "bidirectional"))
      (node (ref "R175") (pin "1") (pinfunction "1_1") (pintype "passive"))
    )
    (net (code "42") (name "/I2C_SCL_10") (class "Default")
      (node (ref "IC15") (pin "17") (pinfunction "SC7_17") (pintype "bidirectional"))
      (node (ref "R178") (pin "1") (pinfunction "1_1") (pintype "passive"))
    )
    (net (code "43") (name "/I2C_SCL_11") (class "Default")
      (node (ref "IC15") (pin "15") (pinfunction "SC6_15") (pintype "bidirectional"))
      (node (ref "R182") (pin "1") (pinfunction "1_1") (pintype "passive"))
    )
    (net (code "45") (name "/I2C_SDA_0") (class "Default")
      (node (ref "IC14") (pin "16") (pinfunction "SD7_16") (pintype "bidirectional"))
      (node (ref "R155") (pin "1") (pinfunction "1_1") (pintype "passive"))
    )
    (net (code "46") (name "/I2C_SDA_1") (class "Default")
      (node (ref "IC14") (pin "12") (pinfunction "SD5_12") (pintype "bidirectional"))
      (node (ref "R157") (pin "1") (pinfunction "1_1") (pintype "passive"))
    )
    (net (code "47") (name "/I2C_SDA_2") (class "Default")
      (node (ref "IC14") (pin "10") (pinfunction "SD4_10") (pintype "bidirectional"))
      (node (ref "R159") (pin "1") (pinfunction "1_1") (pintype "passive"))
    )
    (net (code "48") (name "/I2C_SDA_3") (class "Default")
      (node (ref "IC14") (pin "7") (pinfunction "SD3_7") (pintype "bidirectional"))
      (node (ref "R161") (pin "1") (pinfunction "1_1") (pintype "passive"))
    )
    (net (code "49") (name "/I2C_SDA_4") (class "Default")
      (node (ref "IC14") (pin "5") (pinfunction "SD2_5") (pintype "bidirectional"))
      (node (ref "R163") (pin "1") (pinfunction "1_1") (pintype "passive"))
    )
    (net (code "50") (name "/I2C_SDA_5") (class "Default")
      (node (ref "IC14") (pin "3") (pinfunction "SD1_3") (pintype "bidirectional"))
      (node (ref "R165") (pin "1") (pinfunction "1_1") (pintype "passive"))
    )
    (net (code "51") (name "/I2C_SDA_6") (class "Default")
      (node (ref "IC14") (pin "1") (pinfunction "SD0_1") (pintype "bidirectional"))
      (node (ref "R167") (pin "1") (pinfunction "1_1") (pintype "passive"))
    )
    (net (code "52") (name "/I2C_SDA_7") (class "Default")
      (node (ref "IC14") (pin "14") (pinfunction "SD6_14") (pintype "bidirectional"))
      (node (ref "R169") (pin "1") (pinfunction "1_1") (pintype "passive"))
    )
    (net (code "53") (name "/I2C_SDA_8") (class "Default")
      (node (ref "IC15") (pin "10") (pinfunction "SD4_10") (pintype "bidirectional"))
      (node (ref "R171") (pin "1") (pinfunction "1_1") (pintype "passive"))
    )
    (net (code "54") (name "/I2C_SDA_9") (class "Default")
      (node (ref "IC15") (pin "12") (pinfunction "SD5_12") (pintype "bidirectional"))
      (node (ref "R173") (pin "1") (pinfunction "1_1") (pintype "passive"))
    )
    (net (code "55") (name "/I2C_SDA_10") (class "Default")
      (node (ref "IC15") (pin "16") (pinfunction "SD7_16") (pintype "bidirectional"))
      (node (ref "R176") (pin "1") (pinfunction "1_1") (pintype "passive"))
    )
    (net (code "56") (name "/I2C_SDA_11") (class "Default")
      (node (ref "IC15") (pin "14") (pinfunction "SD6_14") (pintype "bidirectional"))
      (node (ref "R180") (pin "1") (pinfunction "1_1") (pintype "passive"))
    )
    (net (code "58") (name "/I2C_SW_RESET") (class "Default")
      (node (ref "R33") (pin "2") (pinfunction "2_2") (pintype "passive"))
      (node (ref "T21") (pin "1") (pinfunction "G_1") (pintype "passive"))
    )
    (net (code "59") (name "/I2C_SW_RESET2") (class "Default")
      (node (ref "R46") (pin "2") (pinfunction "2_2") (pintype "passive"))
      (node (ref "T22") (pin "1") (pinfunction "G_1") (pintype "passive"))
    )
    (net (code "60") (name "/I2C_SW_RESET_N") (class "Default")
      (node (ref "IC14") (pin "24") (pinfunction "~{RESET}_24") (pintype "input"))
      (node (ref "IC15") (pin "24") (pinfunction "~{RESET}_24") (pintype "input"))
      (node (ref "R151") (pin "1") (pinfunction "1_1") (pintype "passive"))
      (node (ref "T21") (pin "3") (pinfunction "D_3") (pintype "passive"))
      (node (ref "T22") (pin "3") (pinfunction "D_3") (pintype "passive"))
    )
    (net (code "61") (name "/SFP_0.LED") (class "Default")
      (node (ref "IC25") (pin "28") (pinfunction "GPA7_28") (pintype "bidirectional"))
      (node (ref "IC43") (pin "11") (pinfunction "P0_7_11") (pintype "bidirectional"))
    )
    (net (code "62") (name "/SFP_0.LOS") (class "Default")
      (node (ref "IC25") (pin "26") (pinfunction "GPA5_26") (pintype "bidirectional"))
      (node (ref "IC43") (pin "9") (pinfunction "P0_5_9") (pintype "bidirectional"))
    )
    (net (code "63") (name "/SFP_0.MOD_PRESENT") (class "Default")
      (node (ref "IC25") (pin "25") (pinfunction "GPA4_25") (pintype "bidirectional"))
      (node (ref "IC43") (pin "8") (pinfunction "P0_4_8") (pintype "bidirectional"))
    )
    (net (code "64") (name "/SFP_0.RATE_SELECT") (class "Default")
      (node (ref "IC25") (pin "24") (pinfunction "GPA3_24") (pintype "bidirectional"))
      (node (ref "IC43") (pin "7") (pinfunction "P0_3_7") (pintype "bidirectional"))
    )
    (net (code "65") (name "/SFP_0.RATE_SELECT1") (class "Default")
      (node (ref "IC25") (pin "23") (pinfunction "GPA2_23") (pintype "bidirectional"))
      (node (ref "IC43") (pin "6") (pinfunction "P0_2_6") (pintype "bidirectional"))
    )
    (net (code "66") (name "/SFP_0.SCL") (class "Default")
      (node (ref "IC15") (pin "2") (pinfunction "SC0_2") (pintype "bidirectional"))
      (node (ref "R184") (pin "1") (pinfunction "1_1") (pintype "passive"))
    )
    (net (code "67") (name "/SFP_0.SDA") (class "Default")
      (node (ref "IC15") (pin "1") (pinfunction "SD0_1") (pintype "bidirectional"))
      (node (ref "R183") (pin "1") (pinfunction "1_1") (pintype "passive"))
    )
    (net (code "68") (name "/SFP_0.TX_DISABLE") (class "Default")
      (node (ref "IC25") (pin "22") (pinfunction "GPA1_22") (pintype "bidirectional"))
      (node (ref "IC43") (pin "5") (pinfunction "P0_1_5") (pintype "bidirectional"))
    )
    (net (code "69") (name "/SFP_0.TX_FAULT") (class "Default")
      (node (ref "IC25") (pin "21") (pinfunction "GPA0_21") (pintype "bidirectional"))
      (node (ref "IC43") (pin "4") (pinfunction "P0_0_4") (pintype "bidirectional"))
    )
    (net (code "71") (name "/SFP_1.LED") (class "Default")
      (node (ref "IC25") (pin "7") (pinfunction "GPB6_7") (pintype "bidirectional"))
      (node (ref "IC43") (pin "19") (pinfunction "P1_6_19") (pintype "bidirectional"))
    )
    (net (code "72") (name "/SFP_1.LOS") (class "Default")
      (node (ref "IC25") (pin "6") (pinfunction "GPB5_6") (pintype "bidirectional"))
      (node (ref "IC43") (pin "18") (pinfunction "P1_5_18") (pintype "bidirectional"))
    )
    (net (code "73") (name "/SFP_1.MOD_PRESENT") (class "Default")
      (node (ref "IC25") (pin "5") (pinfunction "GPB4_5") (pintype "bidirectional"))
      (node (ref "IC43") (pin "17") (pinfunction "P1_4_17") (pintype "bidirectional"))
    )
    (net (code "74") (name "/SFP_1.RATE_SELECT") (class "Default")
      (node (ref "IC25") (pin "4") (pinfunction "GPB3_4") (pintype "bidirectional"))
      (node (ref "IC43") (pin "16") (pinfunction "P1_3_16") (pintype "bidirectional"))
    )
    (net (code "75") (name "/SFP_1.RATE_SELECT1") (class "Default")
      (node (ref "IC25") (pin "3") (pinfunction "GPB2_3") (pintype "bidirectional"))
      (node (ref "IC43") (pin "15") (pinfunction "P1_2_15") (pintype "bidirectional"))
    )
    (net (code "76") (name "/SFP_1.SCL") (class "Default")
      (node (ref "IC15") (pin "4") (pinfunction "SC1_4") (pintype "bidirectional"))
      (node (ref "R186") (pin "1") (pinfunction "1_1") (pintype "passive"))
    )
    (net (code "77") (name "/SFP_1.SDA") (class "Default")
      (node (ref "IC15") (pin "3") (pinfunction "SD1_3") (pintype "bidirectional"))
      (node (ref "R185") (pin "1") (pinfunction "1_1") (pintype "passive"))
    )
    (net (code "78") (name "/SFP_1.TX_DISABLE") (class "Default")
      (node (ref "IC25") (pin "2") (pinfunction "GPB1_2") (pintype "bidirectional"))
      (node (ref "IC43") (pin "14") (pinfunction "P1_1_14") (pintype "bidirectional"))
    )
    (net (code "79") (name "/SFP_1.TX_FAULT") (class "Default")
      (node (ref "IC25") (pin "1") (pinfunction "GPB0_1") (pintype "bidirectional"))
      (node (ref "IC43") (pin "13") (pinfunction "P1_0_13") (pintype "bidirectional"))
    )
    (net (code "81") (name "/SFP_2.LED") (class "Default")
      (node (ref "IC24") (pin "27") (pinfunction "GPA6_27") (pintype "bidirectional"))
      (node (ref "IC42") (pin "10") (pinfunction "P0_6_10") (pintype "bidirectional"))
    )
    (net (code "82") (name "/SFP_2.LOS") (class "Default")
      (node (ref "IC24") (pin "26") (pinfunction "GPA5_26") (pintype "bidirectional"))
      (node (ref "IC42") (pin "9") (pinfunction "P0_5_9") (pintype "bidirectional"))
    )
    (net (code "83") (name "/SFP_2.MOD_PRESENT") (class "Default")
      (node (ref "IC24") (pin "25") (pinfunction "GPA4_25") (pintype "bidirectional"))
      (node (ref "IC42") (pin "8") (pinfunction "P0_4_8") (pintype "bidirectional"))
    )
    (net (code "84") (name "/SFP_2.RATE_SELECT") (class "Default")
      (node (ref "IC24") (pin "24") (pinfunction "GPA3_24") (pintype "bidirectional"))
      (node (ref "IC42") (pin "7") (pinfunction "P0_3_7") (pintype "bidirectional"))
    )
    (net (code "85") (name "/SFP_2.RATE_SELECT1") (class "Default")
      (node (ref "IC24") (pin "23") (pinfunction "GPA2_23") (pintype "bidirectional"))
      (node (ref "IC42") (pin "6") (pinfunction "P0_2_6") (pintype "bidirectional"))
    )
    (net (code "86") (name "/SFP_2.SCL") (class "Default")
      (node (ref "IC15") (pin "6") (pinfunction "SC2_6") (pintype "bidirectional"))
      (node (ref "R188") (pin "1") (pinfunction "1_1") (pintype "passive"))
    )
    (net (code "87") (name "/SFP_2.SDA") (class "Default")
      (node (ref "IC15") (pin "5") (pinfunction "SD2_5") (pintype "bidirectional"))
      (node (ref "R187") (pin "1") (pinfunction "1_1") (pintype "passive"))
    )
    (net (code "88") (name "/SFP_2.TX_DISABLE") (class "Default")
      (node (ref "IC24") (pin "22") (pinfunction "GPA1_22") (pintype "bidirectional"))
      (node (ref "IC42") (pin "5") (pinfunction "P0_1_5") (pintype "bidirectional"))
    )
    (net (code "89") (name "/SFP_2.TX_FAULT") (class "Default")
      (node (ref "IC24") (pin "21") (pinfunction "GPA0_21") (pintype "bidirectional"))
      (node (ref "IC42") (pin "4") (pinfunction "P0_0_4") (pintype "bidirectional"))
    )
    (net (code "91") (name "/SFP_3.LED") (class "Default")
      (node (ref "IC24") (pin "8") (pinfunction "GPB7_8") (pintype "bidirectional"))
      (node (ref "IC42") (pin "20") (pinfunction "P1_7_20") (pintype "bidirectional"))
    )
    (net (code "92") (name "/SFP_3.LOS") (class "Default")
      (node (ref "IC24") (pin "6") (pinfunction "GPB5_6") (pintype "bidirectional"))
      (node (ref "IC42") (pin "18") (pinfunction "P1_5_18") (pintype "bidirectional"))
    )
    (net (code "93") (name "/SFP_3.MOD_PRESENT") (class "Default")
      (node (ref "IC24") (pin "5") (pinfunction "GPB4_5") (pintype "bidirectional"))
      (node (ref "IC42") (pin "17") (pinfunction "P1_4_17") (pintype "bidirectional"))
    )
    (net (code "94") (name "/SFP_3.RATE_SELECT") (class "Default")
      (node (ref "IC24") (pin "4") (pinfunction "GPB3_4") (pintype "bidirectional"))
      (node (ref "IC42") (pin "16") (pinfunction "P1_3_16") (pintype "bidirectional"))
    )
    (net (code "95") (name "/SFP_3.RATE_SELECT1") (class "Default")
      (node (ref "IC24") (pin "3") (pinfunction "GPB2_3") (pintype "bidirectional"))
      (node (ref "IC42") (pin "15") (pinfunction "P1_2_15") (pintype "bidirectional"))
    )
    (net (code "96") (name "/SFP_3.TX_DISABLE") (class "Default")
      (node (ref "IC24") (pin "2") (pinfunction "GPB1_2") (pintype "bidirectional"))
      (node (ref "IC42") (pin "14") (pinfunction "P1_1_14") (pintype "bidirectional"))
    )
    (net (code "97") (name "/SFP_3.TX_FAULT") (class "Default")
      (node (ref "IC24") (pin "1") (pinfunction "GPB0_1") (pintype "bidirectional"))
      (node (ref "IC42") (pin "13") (pinfunction "P1_0_13") (pintype "bidirectional"))
    )
    (net (code "99") (name "/SHARED_SCL") (class "Default")
      (node (ref "IC15") (pin "8") (pinfunction "SC3_8") (pintype "bidirectional"))
      (node (ref "IC27") (pin "2") (pinfunction "SCL_2") (pintype "input"))
      (node (ref "IC28") (pin "2") (pinfunction "SCL_2") (pintype "input"))
      (node (ref "R190") (pin "1") (pinfunction "1_1") (pintype "passive"))
      (node (ref "R228") (pin "1") (pinfunction "1_1") (pintype "passive"))
      (node (ref "R229") (pin "1") (pinfunction "1_1") (pintype "passive"))
      (node (ref "R231") (pin "1") (pinfunction "1_1") (pintype "passive"))
      (node (ref "R235") (pin "1") (pinfunction "1_1") (pintype "passive"))
      (node (ref "TP3") (pin "1") (pinfunction "1_1") (pintype "bidirectional"))
    )
    (net (code "100") (name "/SHARED_SDA") (class "Default")
      (node (ref "IC15") (pin "7") (pinfunction "SD3_7") (pintype "bidirectional"))
      (node (ref "IC27") (pin "1") (pinfunction "SDA_1") (pintype "bidirectional"))
      (node (ref "IC28") (pin "1") (pinfunction "SDA_1") (pintype "bidirectional"))
      (node (ref "R189") (pin "1") (pinfunction "1_1") (pintype "passive"))
      (node (ref "R230") (pin "1") (pinfunction "1_1") (pintype "passive"))
      (node (ref "R232") (pin "1") (pinfunction "1_1") (pintype "passive"))
      (node (ref "R233") (pin "1") (pinfunction "1_1") (pintype "passive"))
      (node (ref "R234") (pin "1") (pinfunction "1_1") (pintype "passive"))
      (node (ref "TP2") (pin "1") (pinfunction "1_1") (pintype "bidirectional"))
    )
    (net (code "101") (name "/VUSB_PRESENT_N") (class "Default")
      (node (ref "IC25") (pin "27") (pinfunction "GPA6_27") (pintype "bidirectional"))
      (node (ref "IC43") (pin "10") (pinfunction "P0_6_10") (pintype "bidirectional"))
    )
    (net (code "106") (name "GND") (class "Default")
      (node (ref "C186") (pin "1") (pinfunction "1_1") (pintype "passive"))
      (node (ref "C192") (pin "1") (pinfunction "1_1") (pintype "passive"))
      (node (ref "C193") (pin "1") (pinfunction "1_1") (pintype "passive"))
      (node (ref "C196") (pin "1") (pinfunction "1_1") (pintype "passive"))
      (node (ref "C197") (pin "1") (pinfunction "1_1") (pintype "passive"))
      (node (ref "C198") (pin "1") (pinfunction "1_1") (pintype "passive"))
      (node (ref "C203") (pin "1") (pinfunction "1_1") (pintype "passive"))
      (node (ref "C227") (pin "1") (pinfunction "1_1") (pintype "passive"))
      (node (ref "C377") (pin "1") (pinfunction "1_1") (pintype "passive"))
      (node (ref "C378") (pin "1") (pinfunction "1_1") (pintype "passive"))
      (node (ref "C379") (pin "1") (pinfunction "1_1") (pintype "passive"))
      (node (ref "C61") (pin "1") (pinfunction "1_1") (pintype "passive"))
      (node (ref "C62") (pin "1") (pinfunction "1_1") (pintype "passive"))
      (node (ref "IC13") (pin "1") (pinfunction "GND_1") (pintype "power_in"))
      (node (ref "IC14") (pin "18") (pinfunction "A2_18") (pintype "input"))
      (node (ref "IC14") (pin "22") (pinfunction "A0_22") (pintype "input"))
      (node (ref "IC14") (pin "23") (pinfunction "A1_23") (pintype "input"))
      (node (ref "IC14") (pin "25") (pinfunction "EP_25") (pintype "power_in"))
      (node (ref "IC14") (pin "9") (pinfunction "GND_9") (pintype "power_in"))
      (node (ref "IC15") (pin "18") (pinfunction "A2_18") (pintype "input"))
      (node (ref "IC15") (pin "23") (pinfunction "A1_23") (pintype "input"))
      (node (ref "IC15") (pin "25") (pinfunction "EP_25") (pintype "power_in"))
      (node (ref "IC15") (pin "9") (pinfunction "GND_9") (pintype "power_in"))
      (node (ref "IC24") (pin "10") (pinfunction "VSS_10") (pintype "power_in"))
      (node (ref "IC24") (pin "16") (pinfunction "A1_16") (pintype "input"))
      (node (ref "IC24") (pin "17") (pinfunction "A2_17") (pintype "input"))
      (node (ref "IC25") (pin "10") (pinfunction "VSS_10") (pintype "power_in"))
      (node (ref "IC25") (pin "15") (pinfunction "A0_15") (pintype "input"))
      (node (ref "IC25") (pin "16") (pinfunction "A1_16") (pintype "input"))
      (node (ref "IC25") (pin "17") (pinfunction "A2_17") (pintype "input"))
      (node (ref "IC27") (pin "4") (pinfunction "GND_4") (pintype "power_in"))
      (node (ref "IC27") (pin "6") (pinfunction "A1_6") (pintype "input"))
      (node (ref "IC27") (pin "7") (pinfunction "A0_7") (pintype "input"))
      (node (ref "IC28") (pin "4") (pinfunction "GND_4") (pintype "power_in"))
      (node (ref "IC42") (pin "12") (pinfunction "GND_12") (pintype "power_in"))
      (node (ref "IC42") (pin "2") (pinfunction "A1_2") (pintype "input"))
      (node (ref "IC43") (pin "12") (pinfunction "GND_12") (pintype "power_in"))
      (node (ref "IC43") (pin "2") (pinfunction "A1_2") (pintype "input"))
      (node (ref "IC43") (pin "21") (pinfunction "A0_21") (pintype "input"))
      (node (ref "IC44") (pin "2") (pinfunction "VSS_2") (pintype "power_in"))
      (node (ref "IC44") (pin "4") (pinfunction "A1_4") (pintype "input"))
      (node (ref "IC44") (pin "5") (pinfunction "A0_5") (pintype "input"))
      (node (ref "IC45") (pin "1") (pinfunction "A0_1") (pintype "input"))
      (node (ref "IC45") (pin "2") (pinfunction "A1_2") (pintype "input"))
      (node (ref "IC45") (pin "3") (pinfunction "A2_3") (pintype "input"))
      (node (ref "IC45") (pin "4") (pinfunction "VSS_4") (pintype "power_in"))
      (node (ref "IC5") (pin "4") (pinfunction "VSS_4") (pintype "power_in"))
      (node (ref "R120") (pin "2") (pinfunction "2_2") (pintype "passive"))
      (node (ref "R121") (pin "2") (pinfunction "2_2") (pintype "passive"))
      (node (ref "R123") (pin "1") (pinfunction "1_1") (pintype "passive"))
      (node (ref "R33") (pin "1") (pinfunction "1_1") (pintype "passive"))
      (node (ref "R46") (pin "1") (pinfunction "1_1") (pintype "passive"))
      (node (ref "T21") (pin "2") (pinfunction "S_2") (pintype "passive"))
      (node (ref "T22") (pin "2") (pinfunction "S_2") (pintype "passive"))
    )
    (net (code "107") (name "Net-(IC5-SCL)") (class "Default")
      (node (ref "IC5") (pin "6") (pinfunction "SCL_6") (pintype "input"))
      (node (ref "R231") (pin "2") (pinfunction "2_2") (pintype "passive"))
    )
    (net (code "108") (name "Net-(IC5-SDA)") (class "Default")
      (node (ref "IC5") (pin "5") (pinfunction "SDA_5") (pintype "bidirectional"))
      (node (ref "R230") (pin "2") (pinfunction "2_2") (pintype "passive"))
    )
    (net (code "109") (name "Net-(IC13-EN)") (class "Default")
      (node (ref "C186") (pin "2") (pinfunction "2_2") (pintype "passive"))
      (node (ref "IC13") (pin "7") (pinfunction "VREF2_7") (pintype "input"))
      (node (ref "IC13") (pin "8") (pinfunction "EN_8") (pintype "input"))
      (node (ref "R240") (pin "1") (pinfunction "1_1") (pintype "passive"))
    )
    (net (code "110") (name "P1V8") (class "Default")
      (node (ref "C193") (pin "2") (pinfunction "2_2") (pintype "passive"))
      (node (ref "C379") (pin "2") (pinfunction "2_2") (pintype "passive"))
      (node (ref "IC13") (pin "2") (pinfunction "VREF1_2") (pintype "input"))
      (node (ref "IC44") (pin "6") (pinfunction "VCC_6") (pintype "power_in"))
      (node (ref "IC45") (pin "8") (pinfunction "VCC_8") (pintype "power_in"))
      (node (ref "R115") (pin "2") (pinfunction "2_2") (pintype "passive"))
      (node (ref "R116") (pin "2") (pinfunction "2_2") (pintype "passive"))
      (node (ref "R118") (pin "2") (pinfunction "2_2") (pintype "passive"))
      (node (ref "R119") (pin "2") (pinfunction "2_2") (pintype "passive"))
      (node (ref "R122") (pin "2") (pinfunction "2_2") (pintype "passive"))
      (node (ref "R146") (pin "2") (pinfunction "2_2") (pintype "passive"))
      (node (ref "R147") (pin "2") (pinfunction "2_2") (pintype "passive"))
    )
    (net (code "111") (name "P3V3") (class "Default")
      (node (ref "C192") (pin "2") (pinfunction "2_2") (pintype "passive"))
      (node (ref "C196") (pin "2") (pinfunction "2_2") (pintype "passive"))
      (node (ref "C197") (pin "2") (pinfunction "2_2") (pintype "passive"))
      (node (ref "C198") (pin "2") (pinfunction "2_2") (pintype "passive"))
      (node (ref "C203") (pin "2") (pinfunction "2_2") (pintype "passive"))
      (node (ref "C227") (pin "2") (pinfunction "2_2") (pintype "passive"))
      (node (ref "C377") (pin "2") (pinfunction "2_2") (pintype "passive"))
      (node (ref "C378") (pin "2") (pinfunction "2_2") (pintype "passive"))
      (node (ref "C61") (pin "2") (pinfunction "2_2") (pintype "passive"))
      (node (ref "C62") (pin "2") (pinfunction "2_2") (pintype "passive"))
      (node (ref "IC14") (pin "21") (pinfunction "VCC_21") (pintype "power_in"))
      (node (ref "IC15") (pin "21") (pinfunction "VCC_21") (pintype "power_in"))
      (node (ref "IC15") (pin "22") (pinfunction "A0_22") (pintype "input"))
      (node (ref "IC24") (pin "15") (pinfunction "A0_15") (pintype "input"))
      (node (ref "IC24") (pin "9") (pinfunction "VDD_9") (pintype "power_in"))
      (node (ref "IC25") (pin "9") (pinfunction "VDD_9") (pintype "power_in"))
      (node (ref "IC27") (pin "5") (pinfunction "A2_5") (pintype "input"))
      (node (ref "IC27") (pin "8") (pinfunction "+VS_8") (pintype "power_in"))
      (node (ref "IC28") (pin "5") (pinfunction "A2_5") (pintype "input"))
      (node (ref "IC28") (pin "6") (pinfunction "A1_6") (pintype "input"))
      (node (ref "IC28") (pin "7") (pinfunction "A0_7") (pintype "input"))
      (node (ref "IC28") (pin "8") (pinfunction "+VS_8") (pintype "power_in"))
      (node (ref "IC42") (pin "21") (pinfunction "A0_21") (pintype "input"))
      (node (ref "IC42") (pin "24") (pinfunction "VCC_24") (pintype "power_in"))
      (node (ref "IC43") (pin "24") (pinfunction "VCC_24") (pintype "power_in"))
      (node (ref "IC5") (pin "1") (pinfunction "A0_1") (pintype "input"))
      (node (ref "IC5") (pin "2") (pinfunction "A1_2") (pintype "input"))
      (node (ref "IC5") (pin "3") (pinfunction "A2_3") (pintype "input"))
      (node (ref "IC5") (pin "8") (pinfunction "VCC_8") (pintype "power_in"))
      (node (ref "R125") (pin "2") (pinfunction "2_2") (pintype "passive"))
      (node (ref "R131") (pin "1") (pinfunction "1_1") (pintype "passive"))
      (node (ref "R132") (pin "1") (pinfunction "1_1") (pintype "passive"))
      (node (ref "R148") (pin "2") (pinfunction "2_2") (pintype "passive"))
      (node (ref "R149") (pin "2") (pinfunction "2_2") (pintype "passive"))
      (node (ref "R151") (pin "2") (pinfunction "2_2") (pintype "passive"))
      (node (ref "R155") (pin "2") (pinfunction "2_2") (pintype "passive"))
      (node (ref "R156") (pin "2") (pinfunction "2_2") (pintype "passive"))
      (node (ref "R157") (pin "2") (pinfunction "2_2") (pintype "passive"))
      (node (ref "R158") (pin "2") (pinfunction "2_2") (pintype "passive"))
      (node (ref "R159") (pin "2") (pinfunction "2_2") (pintype "passive"))
      (node (ref "R160") (pin "2") (pinfunction "2_2") (pintype "passive"))
      (node (ref "R161") (pin "2") (pinfunction "2_2") (pintype "passive"))
      (node (ref "R162") (pin "2") (pinfunction "2_2") (pintype "passive"))
      (node (ref "R163") (pin "2") (pinfunction "2_2") (pintype "passive"))
      (node (ref "R164") (pin "2") (pinfunction "2_2") (pintype "passive"))
      (node (ref "R165") (pin "2") (pinfunction "2_2") (pintype "passive"))
      (node (ref "R166") (pin "2") (pinfunction "2_2") (pintype "passive"))
      (node (ref "R167") (pin "2") (pinfunction "2_2") (pintype "passive"))
      (node (ref "R168") (pin "2") (pinfunction "2_2") (pintype "passive"))
      (node (ref "R169") (pin "2") (pinfunction "2_2") (pintype "passive"))
      (node (ref "R170") (pin "2") (pinfunction "2_2") (pintype "passive"))
      (node (ref "R171") (pin "2") (pinfunction "2_2") (pintype "passive"))
      (node (ref "R172") (pin "2") (pinfunction "2_2") (pintype "passive"))
      (node (ref "R173") (pin "2") (pinfunction "2_2") (pintype "passive"))
      (node (ref "R175") (pin "2") (pinfunction "2_2") (pintype "passive"))
      (node (ref "R176") (pin "2") (pinfunction "2_2") (pintype "passive"))
      (node (ref "R178") (pin "2") (pinfunction "2_2") (pintype "passive"))
      (node (ref "R180") (pin "2") (pinfunction "2_2") (pintype "passive"))
      (node (ref "R182") (pin "2") (pinfunction "2_2") (pintype "passive"))
      (node (ref "R183") (pin "2") (pinfunction "2_2") (pintype "passive"))
      (node (ref "R184") (pin "2") (pinfunction "2_2") (pintype "passive"))
      (node (ref "R185") (pin "2") (pinfunction "2_2") (pintype "passive"))
      (node (ref "R186") (pin "2") (pinfunction "2_2") (pintype "passive"))
      (node (ref "R187") (pin "2") (pinfunction "2_2") (pintype "passive"))
      (node (ref "R188") (pin "2") (pinfunction "2_2") (pintype "passive"))
      (node (ref "R189") (pin "2") (pinfunction "2_2") (pintype "passive"))
      (node (ref "R190") (pin "2") (pinfunction "2_2") (pintype "passive"))
      (node (ref "R240") (pin "2") (pinfunction "2_2") (pintype "passive"))
    )
    (net (code "112") (name "unconnected-(IC5-NC-Pad7)") (class "Default")
      (node (ref "IC5") (pin "7") (pinfunction "NC_7") (pintype "passive+no_connect"))
    )
    (net (code "113") (name "unconnected-(IC24-INTB-Pad19)") (class "Default")
      (node (ref "IC24") (pin "19") (pinfunction "INTB_19") (pintype "output+no_connect"))
    )
    (net (code "114") (name "unconnected-(IC24-NC-Pad11)") (class "Default")
      (node (ref "IC24") (pin "11") (pinfunction "NC_11") (pintype "passive+no_connect"))
    )
    (net (code "115") (name "unconnected-(IC24-NC-Pad14)") (class "Default")
      (node (ref "IC24") (pin "14") (pinfunction "NC_14") (pintype "passive+no_connect"))
    )
    (net (code "116") (name "unconnected-(IC25-INTB-Pad19)") (class "Default")
      (node (ref "IC25") (pin "19") (pinfunction "INTB_19") (pintype "output+no_connect"))
    )
    (net (code "117") (name "unconnected-(IC25-NC-Pad11)") (class "Default")
      (node (ref "IC25") (pin "11") (pinfunction "NC_11") (pintype "passive+no_connect"))
    )
    (net (code "118") (name "unconnected-(IC25-NC-Pad14)") (class "Default")
      (node (ref "IC25") (pin "14") (pinfunction "NC_14") (pintype "passive+no_connect"))
    )
    (net (code "119") (name "unconnected-(IC27-O.S.-Pad3)") (class "Default")
      (node (ref "IC27") (pin "3") (pinfunction "O.S._3") (pintype "output"))
    )
    (net (code "120") (name "unconnected-(IC28-O.S.-Pad3)") (class "Default")
      (node (ref "IC28") (pin "3") (pinfunction "O.S._3") (pintype "output"))
    )
    (net (code "121") (name "unconnected-(IC45-NC-Pad7)") (class "Default")
      (node (ref "IC45") (pin "7") (pinfunction "NC_7") (pintype "passive+no_connect"))
    )
    (net (code "122") (name "unconnected-(R234-Pad2)") (class "Default")
      (node (ref "R234") (pin "2") (pinfunction "2_2") (pintype "passive"))
    )
    (net (code "123") (name "unconnected-(R235-Pad2)") (class "Default")
      (node (ref "R235") (pin "2") (pinfunction "2_2") (pintype "passive"))
    )
  )
)
